# glowball.net
KiCad netlist of a schematic drawn in EAGLE
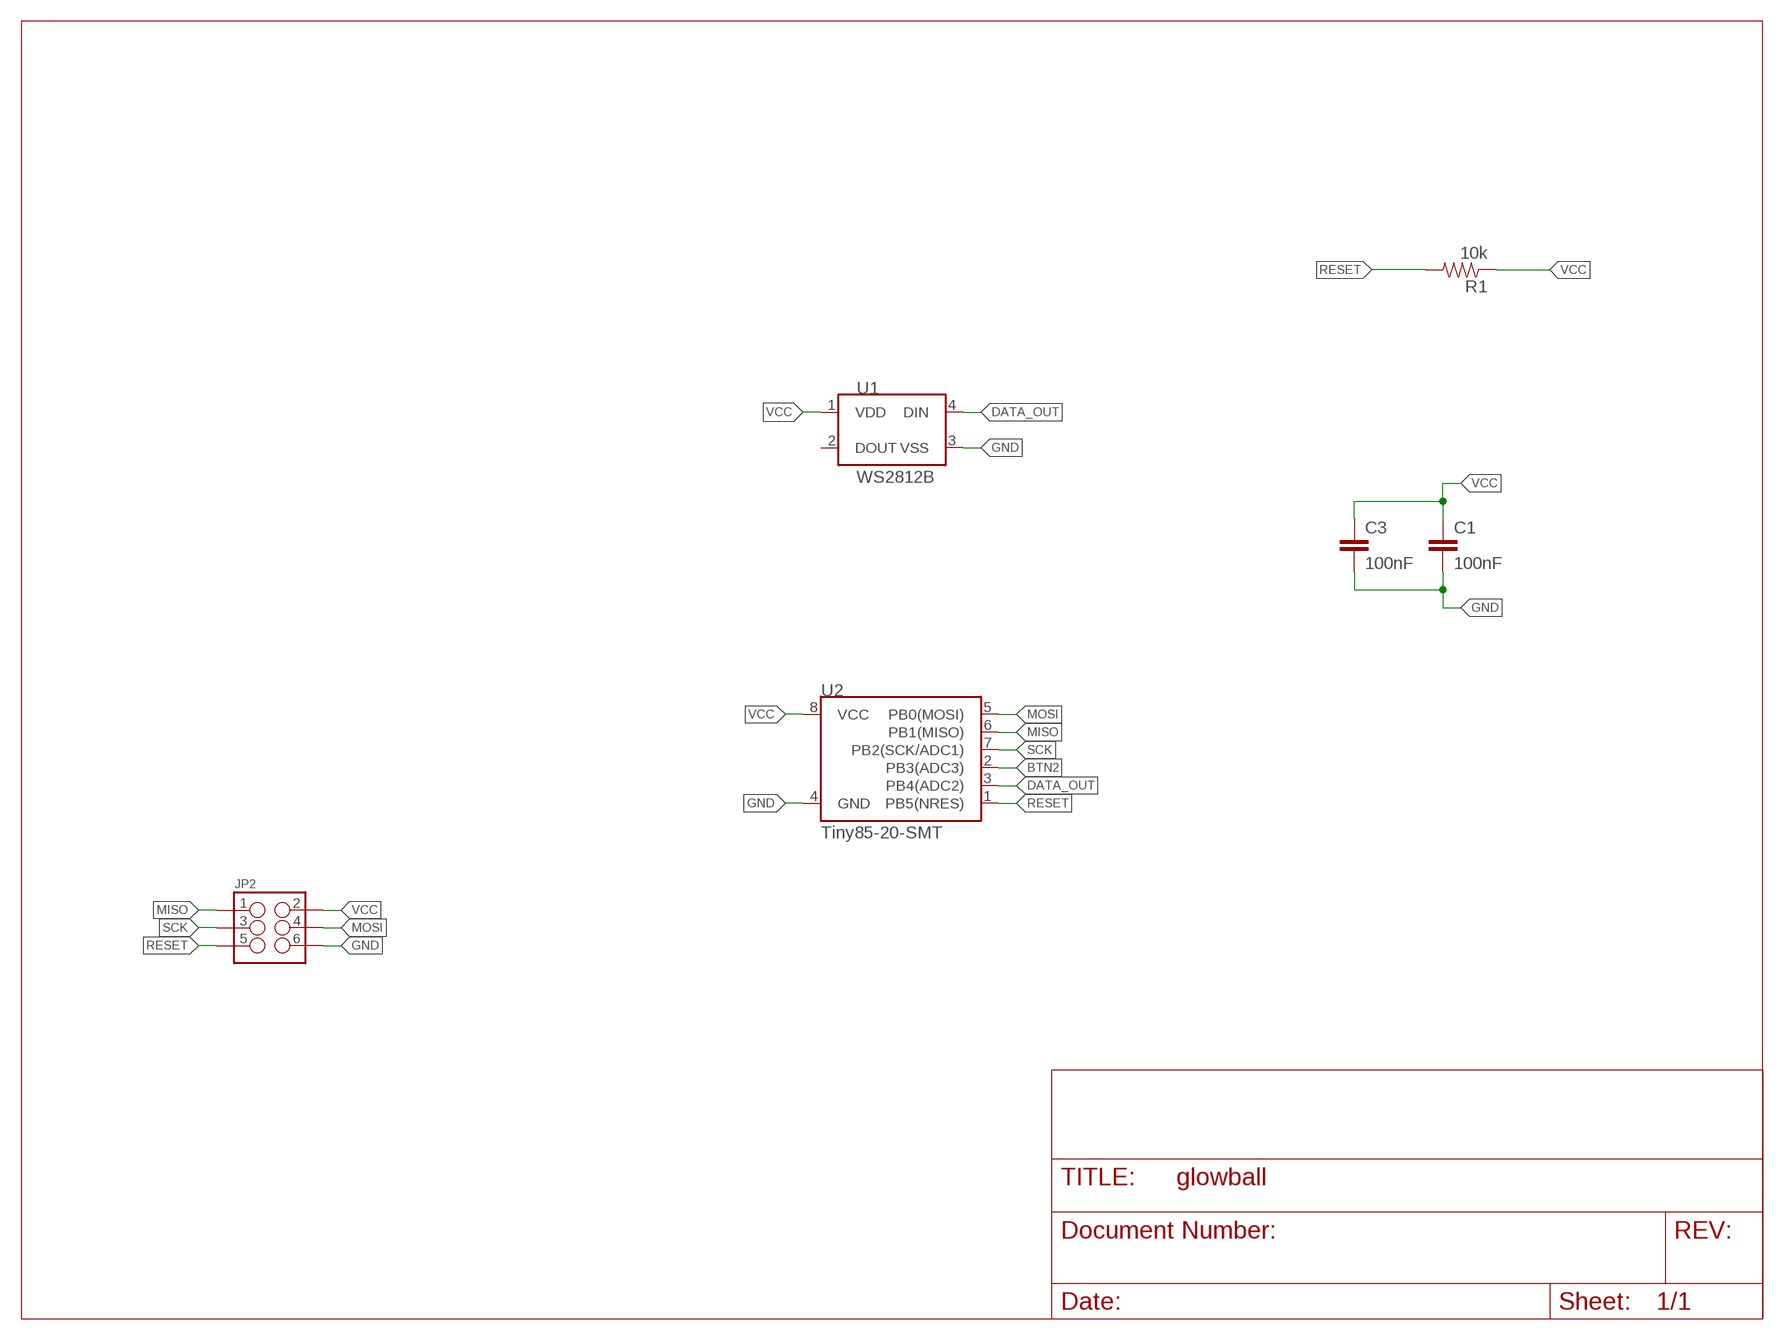
[diagram p0: schematic, sheet 1]

(export (version "E")
  (design (tool "Eeschema 10.0.6"))
  (components
    (comp (ref "C1")
      (value "100nF")
      (footprint "eagle-import:0805")
      (fields (field (name "PARTNO") "C0805C104K8RACTU"))
      (libsource (lib "eagle-import") (part "CAP0805"))
    )
    (comp (ref "C3")
      (value "100nF")
      (footprint "eagle-import:0805")
      (fields (field (name "PARTNO") "C0805C104K8RACTU"))
      (libsource (lib "eagle-import") (part "CAP0805"))
    )
    (comp (ref "JP2")
      (value "M03X2")
      (footprint "eagle-import:2X3_SMD")
      (fields (field (name "PARTNO") "M20-9980346"))
      (libsource (lib "eagle-import") (part "M03X2"))
    )
    (comp (ref "R1")
      (value "10k")
      (footprint "eagle-import:0805")
      (fields (field (name "PARTNO") "RMCF0805FT10K0"))
      (libsource (lib "eagle-import") (part "RESISTOR0805-RES"))
    )
    (comp (ref "U1")
      (value "WS2812B")
      (footprint "eagle-import:WS2812B")
      (libsource (lib "eagle-import") (part "WS2812B"))
    )
    (comp (ref "U2")
      (value "Tiny85-20-SMT")
      (footprint "eagle-import:SO08-EIAJ")
      (fields (field (name "PARTNO") "ATTINY85-20SUR"))
      (libsource (lib "eagle-import") (part "ATTINY45TINY85-20-SMT"))
    )
  )
  (nets
    (net (code "1") (name "BTN2") (class "Default")
      (node (ref "U2") (pin "2") (pinfunction "PB3(ADC3)_2") (pintype "bidirectional"))
    )
    (net (code "2") (name "DATA_OUT") (class "Default")
      (node (ref "U1") (pin "4") (pinfunction "DIN_4") (pintype "bidirectional"))
      (node (ref "U2") (pin "3") (pinfunction "PB4(ADC2)_3") (pintype "bidirectional"))
    )
    (net (code "3") (name "GND") (class "Default")
      (node (ref "C1") (pin "2") (pinfunction "2_2") (pintype "passive"))
      (node (ref "C3") (pin "2") (pinfunction "2_2") (pintype "passive"))
      (node (ref "JP2") (pin "6") (pinfunction "6_6") (pintype "bidirectional"))
      (node (ref "U1") (pin "3") (pinfunction "VSS_3") (pintype "bidirectional"))
      (node (ref "U2") (pin "4") (pinfunction "GND_4") (pintype "bidirectional"))
    )
    (net (code "4") (name "MISO") (class "Default")
      (node (ref "JP2") (pin "1") (pinfunction "1_1") (pintype "bidirectional"))
      (node (ref "U2") (pin "6") (pinfunction "PB1(MISO)_6") (pintype "bidirectional"))
    )
    (net (code "5") (name "MOSI") (class "Default")
      (node (ref "JP2") (pin "4") (pinfunction "4_4") (pintype "bidirectional"))
      (node (ref "U2") (pin "5") (pinfunction "PB0(MOSI)_5") (pintype "bidirectional"))
    )
    (net (code "6") (name "RESET") (class "Default")
      (node (ref "JP2") (pin "5") (pinfunction "5_5") (pintype "bidirectional"))
      (node (ref "R1") (pin "2") (pinfunction "2_2") (pintype "passive"))
      (node (ref "U2") (pin "1") (pinfunction "PB5(NRES)_1") (pintype "bidirectional"))
    )
    (net (code "7") (name "SCK") (class "Default")
      (node (ref "JP2") (pin "3") (pinfunction "3_3") (pintype "bidirectional"))
      (node (ref "U2") (pin "7") (pinfunction "PB2(SCK/ADC1)_7") (pintype "bidirectional"))
    )
    (net (code "8") (name "VCC") (class "Default")
      (node (ref "C1") (pin "1") (pinfunction "1_1") (pintype "passive"))
      (node (ref "C3") (pin "1") (pinfunction "1_1") (pintype "passive"))
      (node (ref "JP2") (pin "2") (pinfunction "2_2") (pintype "bidirectional"))
      (node (ref "R1") (pin "1") (pinfunction "1_1") (pintype "passive"))
      (node (ref "U1") (pin "1") (pinfunction "VDD_1") (pintype "bidirectional"))
      (node (ref "U2") (pin "8") (pinfunction "VCC_8") (pintype "bidirectional"))
    )
    (net (code "9") (name "unconnected-(U1-DOUT-Pad2)") (class "Default")
      (node (ref "U1") (pin "2") (pinfunction "DOUT_2") (pintype "bidirectional"))
    )
  )
)
